# RPi_Lego_Server_Daughter_Board_v1.net
KiCad netlist of a schematic drawn in EAGLE
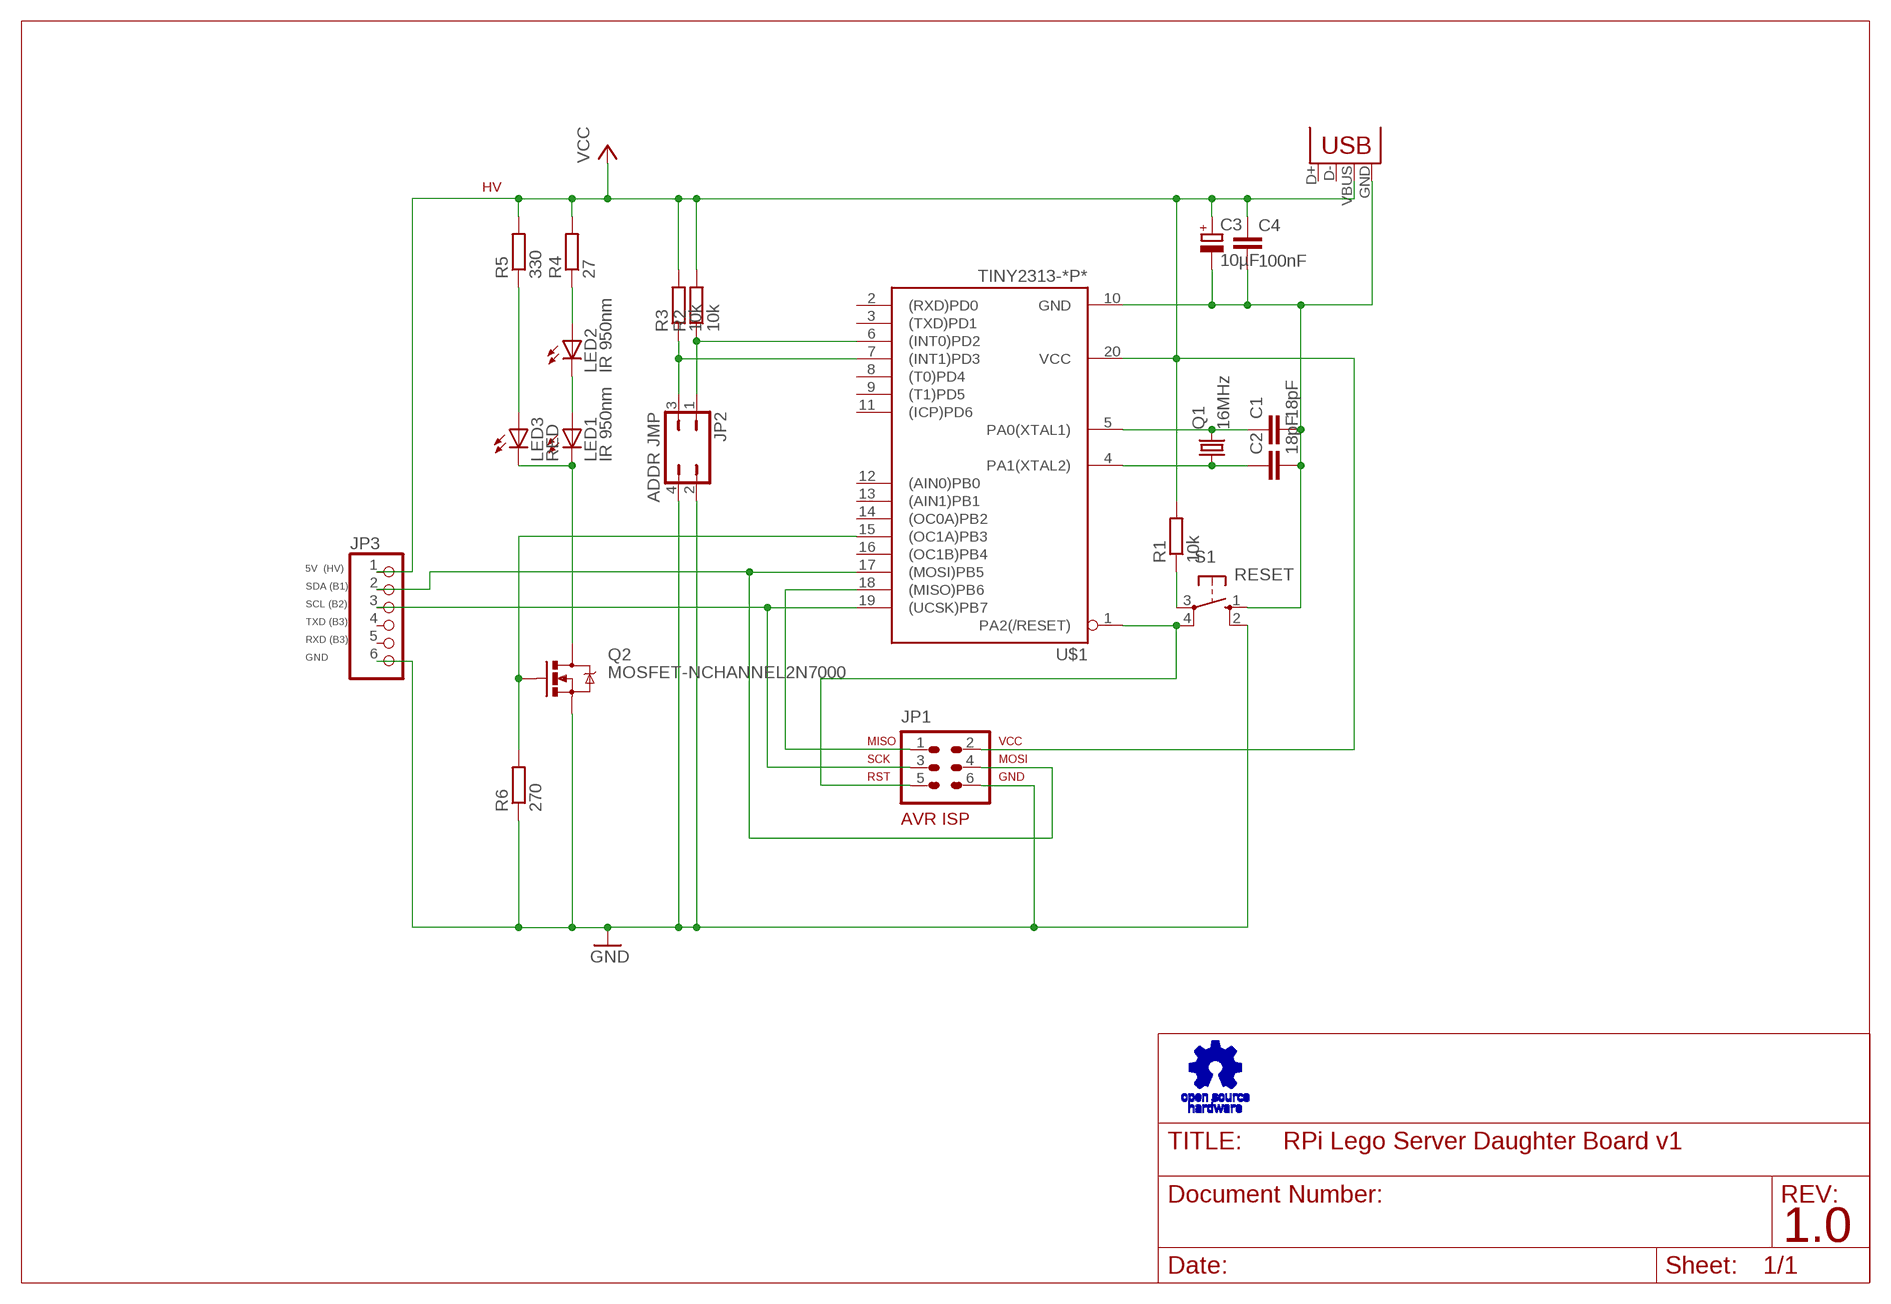
[diagram p0: schematic, sheet 1]

(export (version "E")
  (design (tool "Eeschema 10.0.6"))
  (components
    (comp (ref "C1")
      (value "18pF")
      (footprint "eagle-import:C025-025X050")
      (libsource (lib "eagle-import") (part "C-EU025-025X050"))
    )
    (comp (ref "C2")
      (value "18pF")
      (footprint "eagle-import:C025-025X050")
      (libsource (lib "eagle-import") (part "C-EU025-025X050"))
    )
    (comp (ref "C3")
      (value "10µF")
      (footprint "eagle-import:E2,5-6")
      (libsource (lib "eagle-import") (part "CPOL-EUE2.5-6"))
    )
    (comp (ref "C4")
      (value "100nF")
      (footprint "eagle-import:C050-030X075")
      (libsource (lib "eagle-import") (part "C-EU050-030X075"))
    )
    (comp (ref "JP1")
      (value "AVR-ISP-6VERT")
      (footprint "eagle-import:AVR-ISP-6")
      (libsource (lib "eagle-import") (part "AVR-ISP-6VERT"))
    )
    (comp (ref "JP2")
      (value "ADDR JMP")
      (footprint "eagle-import:JP2Q")
      (libsource (lib "eagle-import") (part "JP2Q"))
    )
    (comp (ref "JP3")
      (value "PINHD-1X6")
      (footprint "eagle-import:1X06")
      (libsource (lib "eagle-import") (part "PINHD-1X6"))
    )
    (comp (ref "JP4")
      (value "USB-B")
      (footprint "eagle-import:USB-B-PTH")
      (libsource (lib "eagle-import") (part "USBPTH"))
    )
    (comp (ref "LED1")
      (value "IR 950nm")
      (footprint "eagle-import:LED5MM")
      (libsource (lib "eagle-import") (part "LED5MM"))
    )
    (comp (ref "LED2")
      (value "IR 950nm")
      (footprint "eagle-import:LED5MM")
      (libsource (lib "eagle-import") (part "LED5MM"))
    )
    (comp (ref "LED3")
      (value "RED")
      (footprint "eagle-import:LED3MM")
      (libsource (lib "eagle-import") (part "LED3MM"))
    )
    (comp (ref "Q1")
      (value "16MHz")
      (footprint "eagle-import:HC49_S")
      (libsource (lib "eagle-import") (part "CRYSTALHC49S"))
    )
    (comp (ref "Q2")
      (value "MOSFET-NCHANNEL2N7000")
      (footprint "eagle-import:TO-92")
      (libsource (lib "eagle-import") (part "MOSFET-NCHANNEL2N7000"))
    )
    (comp (ref "R1")
      (value "10k")
      (footprint "eagle-import:0207_10")
      (libsource (lib "eagle-import") (part "R-EU_0207_10"))
    )
    (comp (ref "R2")
      (value "10k")
      (footprint "eagle-import:0207_10")
      (libsource (lib "eagle-import") (part "R-EU_0207_10"))
    )
    (comp (ref "R3")
      (value "10k")
      (footprint "eagle-import:0207_10")
      (libsource (lib "eagle-import") (part "R-EU_0207_10"))
    )
    (comp (ref "R4")
      (value "27")
      (footprint "eagle-import:0207_10")
      (libsource (lib "eagle-import") (part "R-EU_0207_10"))
    )
    (comp (ref "R5")
      (value "330")
      (footprint "eagle-import:0207_10")
      (libsource (lib "eagle-import") (part "R-EU_0207_10"))
    )
    (comp (ref "R6")
      (value "270")
      (footprint "eagle-import:0207_10")
      (libsource (lib "eagle-import") (part "R-EU_0207_10"))
    )
    (comp (ref "S1")
      (value "RESET")
      (footprint "eagle-import:B3F-10XX")
      (fields (field (name "MPN") "B3F-1000"))
      (libsource (lib "eagle-import") (part "10-XX"))
    )
    (comp (ref "U$1")
      (value "TINY2313-*P*")
      (footprint "eagle-import:DIL20")
      (libsource (lib "eagle-import") (part "TINY2313-P"))
    )
  )
  (nets
    (net (code "1") (name "GND") (class "Default")
      (node (ref "C1") (pin "2") (pinfunction "2_2") (pintype "passive"))
      (node (ref "C2") (pin "2") (pinfunction "2_2") (pintype "passive"))
      (node (ref "C3") (pin "-") (pinfunction "-_-") (pintype "passive"))
      (node (ref "C4") (pin "2") (pinfunction "2_2") (pintype "passive"))
      (node (ref "JP1") (pin "6") (pinfunction "6_6") (pintype "passive"))
      (node (ref "JP2") (pin "2") (pinfunction "2_2") (pintype "passive"))
      (node (ref "JP2") (pin "4") (pinfunction "4_4") (pintype "passive"))
      (node (ref "JP3") (pin "6") (pinfunction "6_6") (pintype "passive"))
      (node (ref "JP4") (pin "GND") (pinfunction "GND_GND") (pintype "bidirectional"))
      (node (ref "Q2") (pin "1") (pinfunction "S_1") (pintype "passive"))
      (node (ref "R6") (pin "1") (pinfunction "1_1") (pintype "passive"))
      (node (ref "S1") (pin "1") (pinfunction "S_1") (pintype "passive"))
      (node (ref "S1") (pin "2") (pinfunction "S1_2") (pintype "passive"))
      (node (ref "U$1") (pin "10") (pinfunction "GND_10") (pintype "power_in"))
    )
    (net (code "2") (name "Net-(LED1-C)") (class "Default")
      (node (ref "LED1") (pin "K") (pinfunction "C_K") (pintype "passive"))
      (node (ref "LED3") (pin "K") (pinfunction "C_K") (pintype "passive"))
      (node (ref "Q2") (pin "3") (pinfunction "D_3") (pintype "passive"))
    )
    (net (code "3") (name "Net-(LED2-C)") (class "Default")
      (node (ref "LED1") (pin "A") (pinfunction "A_A") (pintype "passive"))
      (node (ref "LED2") (pin "K") (pinfunction "C_K") (pintype "passive"))
    )
    (net (code "4") (name "Net-(LED2-PadA)") (class "Default")
      (node (ref "LED2") (pin "A") (pinfunction "A_A") (pintype "passive"))
      (node (ref "R4") (pin "1") (pinfunction "1_1") (pintype "passive"))
    )
    (net (code "5") (name "Net-(LED3-PadA)") (class "Default")
      (node (ref "LED3") (pin "A") (pinfunction "A_A") (pintype "passive"))
      (node (ref "R5") (pin "1") (pinfunction "1_1") (pintype "passive"))
    )
    (net (code "6") (name "Net-(Q2-G)") (class "Default")
      (node (ref "Q2") (pin "2") (pinfunction "G_2") (pintype "passive"))
      (node (ref "R6") (pin "2") (pinfunction "2_2") (pintype "passive"))
      (node (ref "U$1") (pin "15") (pinfunction "(OC1A)PB3_15") (pintype "bidirectional"))
    )
    (net (code "7") (name "Net-(S1-P)") (class "Default")
      (node (ref "R1") (pin "1") (pinfunction "1_1") (pintype "passive"))
      (node (ref "S1") (pin "3") (pinfunction "P_3") (pintype "passive"))
    )
    (net (code "8") (name "Net-(S1-P1)") (class "Default")
      (node (ref "JP1") (pin "5") (pinfunction "5_5") (pintype "passive"))
      (node (ref "S1") (pin "4") (pinfunction "P1_4") (pintype "passive"))
      (node (ref "U$1") (pin "1") (pinfunction "PA2(/RESET)_1") (pintype "input"))
    )
    (net (code "9") (name "Net-(U$1-(INT0)PD2)") (class "Default")
      (node (ref "JP2") (pin "1") (pinfunction "1_1") (pintype "passive"))
      (node (ref "R2") (pin "1") (pinfunction "1_1") (pintype "passive"))
      (node (ref "U$1") (pin "6") (pinfunction "(INT0)PD2_6") (pintype "bidirectional"))
    )
    (net (code "10") (name "Net-(U$1-(INT1)PD3)") (class "Default")
      (node (ref "JP2") (pin "3") (pinfunction "3_3") (pintype "passive"))
      (node (ref "R3") (pin "1") (pinfunction "1_1") (pintype "passive"))
      (node (ref "U$1") (pin "7") (pinfunction "(INT1)PD3_7") (pintype "bidirectional"))
    )
    (net (code "11") (name "Net-(U$1-(MISO)PB6)") (class "Default")
      (node (ref "JP1") (pin "1") (pinfunction "1_1") (pintype "passive"))
      (node (ref "U$1") (pin "18") (pinfunction "(MISO)PB6_18") (pintype "bidirectional"))
    )
    (net (code "12") (name "Net-(U$1-(MOSI)PB5)") (class "Default")
      (node (ref "JP1") (pin "4") (pinfunction "4_4") (pintype "passive"))
      (node (ref "JP3") (pin "2") (pinfunction "2_2") (pintype "passive"))
      (node (ref "U$1") (pin "17") (pinfunction "(MOSI)PB5_17") (pintype "bidirectional"))
    )
    (net (code "13") (name "Net-(U$1-(UCSK)PB7)") (class "Default")
      (node (ref "JP1") (pin "3") (pinfunction "3_3") (pintype "passive"))
      (node (ref "JP3") (pin "3") (pinfunction "3_3") (pintype "passive"))
      (node (ref "U$1") (pin "19") (pinfunction "(UCSK)PB7_19") (pintype "bidirectional"))
    )
    (net (code "14") (name "Net-(U$1-PA0(XTAL1))") (class "Default")
      (node (ref "C1") (pin "1") (pinfunction "1_1") (pintype "passive"))
      (node (ref "Q1") (pin "2") (pinfunction "2_2") (pintype "passive"))
      (node (ref "U$1") (pin "5") (pinfunction "PA0(XTAL1)_5") (pintype "bidirectional"))
    )
    (net (code "15") (name "Net-(U$1-PA1(XTAL2))") (class "Default")
      (node (ref "C2") (pin "1") (pinfunction "1_1") (pintype "passive"))
      (node (ref "Q1") (pin "1") (pinfunction "1_1") (pintype "passive"))
      (node (ref "U$1") (pin "4") (pinfunction "PA1(XTAL2)_4") (pintype "bidirectional"))
    )
    (net (code "16") (name "VCC") (class "Default")
      (node (ref "C3") (pin "+") (pinfunction "+_+") (pintype "passive"))
      (node (ref "C4") (pin "1") (pinfunction "1_1") (pintype "passive"))
      (node (ref "JP1") (pin "2") (pinfunction "2_2") (pintype "passive"))
      (node (ref "JP3") (pin "1") (pinfunction "1_1") (pintype "passive"))
      (node (ref "JP4") (pin "VBUS") (pinfunction "VBUS_VBUS") (pintype "bidirectional"))
      (node (ref "R1") (pin "2") (pinfunction "2_2") (pintype "passive"))
      (node (ref "R2") (pin "2") (pinfunction "2_2") (pintype "passive"))
      (node (ref "R3") (pin "2") (pinfunction "2_2") (pintype "passive"))
      (node (ref "R4") (pin "2") (pinfunction "2_2") (pintype "passive"))
      (node (ref "R5") (pin "2") (pinfunction "2_2") (pintype "passive"))
      (node (ref "U$1") (pin "20") (pinfunction "VCC_20") (pintype "power_in"))
    )
    (net (code "17") (name "unconnected-(JP3-Pad4)") (class "Default")
      (node (ref "JP3") (pin "4") (pinfunction "4_4") (pintype "passive"))
    )
    (net (code "18") (name "unconnected-(JP3-Pad5)") (class "Default")
      (node (ref "JP3") (pin "5") (pinfunction "5_5") (pintype "passive"))
    )
    (net (code "19") (name "unconnected-(JP4-PadD+)") (class "Default")
      (node (ref "JP4") (pin "D+") (pinfunction "D+_D+") (pintype "bidirectional"))
    )
    (net (code "20") (name "unconnected-(JP4-PadD-)") (class "Default")
      (node (ref "JP4") (pin "D-") (pinfunction "D-_D-") (pintype "bidirectional"))
    )
    (net (code "21") (name "unconnected-(U$1-(AIN0)PB0-Pad12)") (class "Default")
      (node (ref "U$1") (pin "12") (pinfunction "(AIN0)PB0_12") (pintype "bidirectional"))
    )
    (net (code "22") (name "unconnected-(U$1-(AIN1)PB1-Pad13)") (class "Default")
      (node (ref "U$1") (pin "13") (pinfunction "(AIN1)PB1_13") (pintype "bidirectional"))
    )
    (net (code "23") (name "unconnected-(U$1-(ICP)PD6-Pad11)") (class "Default")
      (node (ref "U$1") (pin "11") (pinfunction "(ICP)PD6_11") (pintype "bidirectional"))
    )
    (net (code "24") (name "unconnected-(U$1-(OC0A)PB2-Pad14)") (class "Default")
      (node (ref "U$1") (pin "14") (pinfunction "(OC0A)PB2_14") (pintype "bidirectional"))
    )
    (net (code "25") (name "unconnected-(U$1-(OC1B)PB4-Pad16)") (class "Default")
      (node (ref "U$1") (pin "16") (pinfunction "(OC1B)PB4_16") (pintype "bidirectional"))
    )
    (net (code "26") (name "unconnected-(U$1-(RXD)PD0-Pad2)") (class "Default")
      (node (ref "U$1") (pin "2") (pinfunction "(RXD)PD0_2") (pintype "bidirectional"))
    )
    (net (code "27") (name "unconnected-(U$1-(T0)PD4-Pad8)") (class "Default")
      (node (ref "U$1") (pin "8") (pinfunction "(T0)PD4_8") (pintype "bidirectional"))
    )
    (net (code "28") (name "unconnected-(U$1-(T1)PD5-Pad9)") (class "Default")
      (node (ref "U$1") (pin "9") (pinfunction "(T1)PD5_9") (pintype "bidirectional"))
    )
    (net (code "29") (name "unconnected-(U$1-(TXD)PD1-Pad3)") (class "Default")
      (node (ref "U$1") (pin "3") (pinfunction "(TXD)PD1_3") (pintype "bidirectional"))
    )
  )
)
